# Power_Sensing.net
KiCad netlist of a schematic drawn in Altium Designer
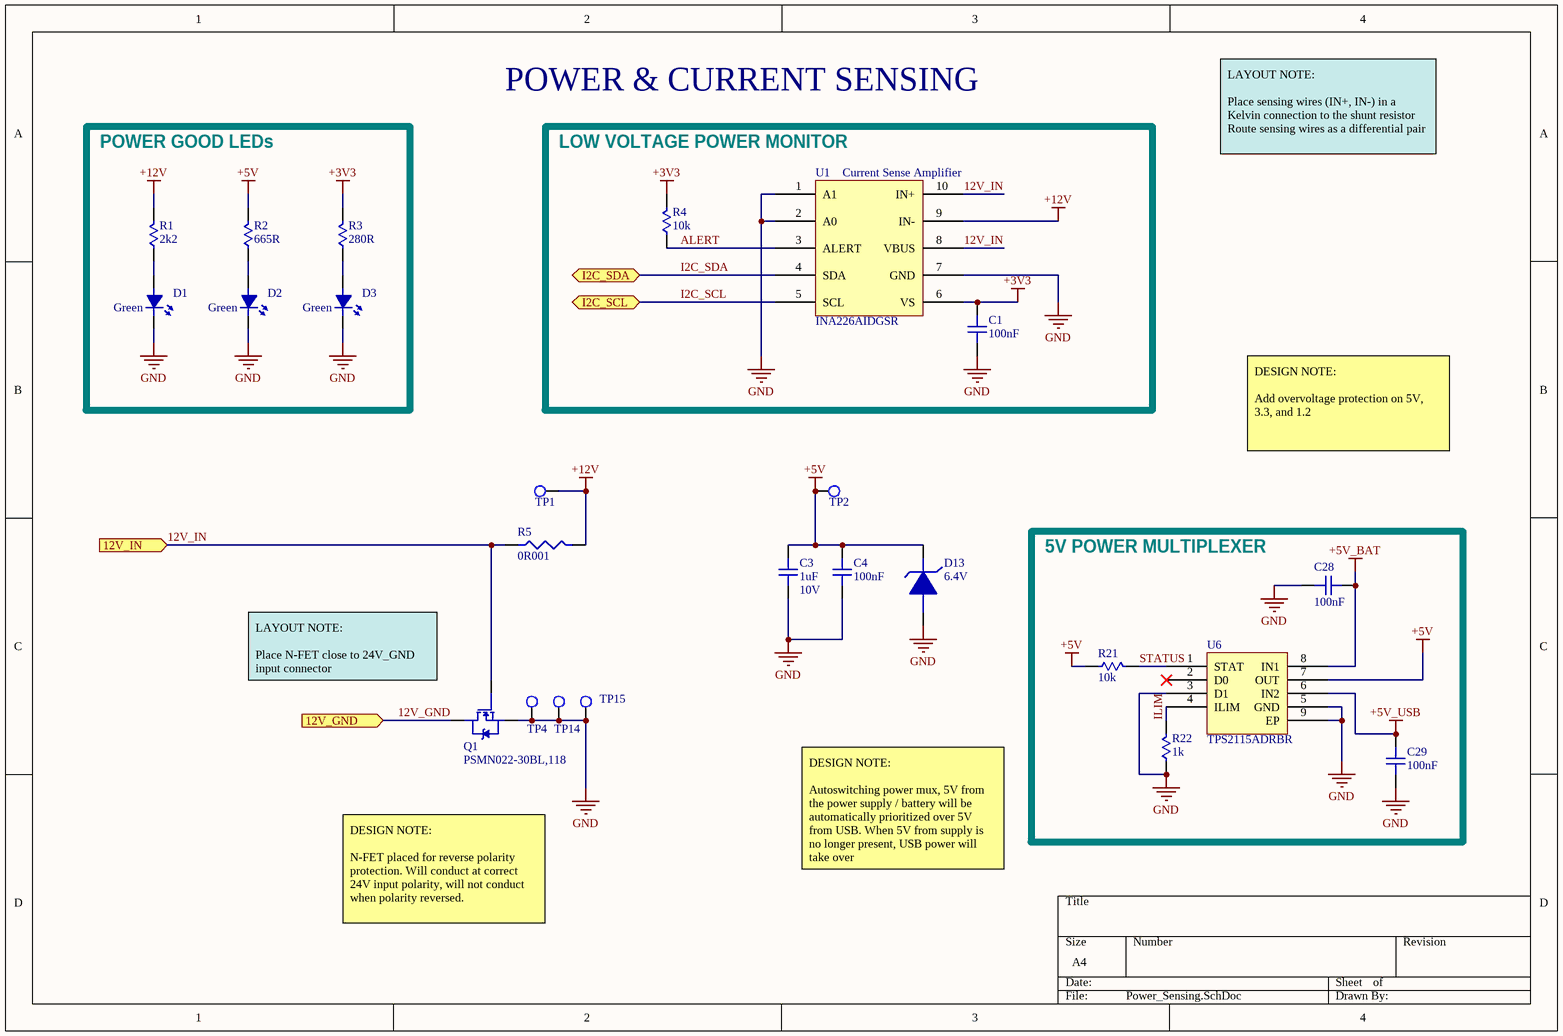
[diagram p0: Power_Sensing.SchDoc]

(export (version "E")
  (design (tool "Eeschema 10.0.6"))
  (components
    (comp (ref "C1")
      (value "100nF")
      (footprint "C0402")
      (description "CAP MLCC 0.1uF 10V X5R 0402 20% SMD 0402 85C Paper T/R")
      (fields
        (field (name "MANUFACTURER") "Samsung")
        (field (name "MANUFACTURER PART NUMBER") "CL05A104MP5NNNC")
      )
      (libsource (lib "PHANTOM_LIBRARY") (part "CL05A104MP5NNNC"))
    )
    (comp (ref "C3")
      (value "1uF")
      (footprint "C0402")
      (description "CAP MLCC 1uF 10V 0402 X5R 20% SMD 0402 85C Paper T/R")
      (fields
        (field (name "MANUFACTURER") "Samsung")
        (field (name "MANUFACTURER PART NUMBER") "CL05A105MP5NNNC")
        (field (name "VOLTAGE RATING") "10V")
      )
      (libsource (lib "PHANTOM_LIBRARY") (part "CL05A105MP5NNNC"))
    )
    (comp (ref "C4")
      (value "100nF")
      (footprint "C0402")
      (description "CAP MLCC 0.1uF 10V X5R 0402 20% SMD 0402 85C Paper T/R")
      (fields
        (field (name "MANUFACTURER") "Samsung")
        (field (name "MANUFACTURER PART NUMBER") "CL05A104MP5NNNC")
      )
      (libsource (lib "PHANTOM_LIBRARY") (part "CL05A104MP5NNNC"))
    )
    (comp (ref "C28")
      (value "100nF")
      (footprint "C0402")
      (description "CAP MLCC 0.1uF 10V X5R 0402 20% SMD 0402 85C Paper T/R")
      (fields
        (field (name "MANUFACTURER") "Samsung")
        (field (name "MANUFACTURER PART NUMBER") "CL05A104MP5NNNC")
      )
      (libsource (lib "PHANTOM_LIBRARY") (part "CL05A104MP5NNNC"))
    )
    (comp (ref "C29")
      (value "100nF")
      (footprint "C0402")
      (description "CAP MLCC 0.1uF 10V X5R 0402 20% SMD 0402 85C Paper T/R")
      (fields
        (field (name "MANUFACTURER") "Samsung")
        (field (name "MANUFACTURER PART NUMBER") "CL05A104MP5NNNC")
      )
      (libsource (lib "PHANTOM_LIBRARY") (part "CL05A104MP5NNNC"))
    )
    (comp (ref "D1")
      (value "Green")
      (footprint "LED_0603")
      (description "LED GREEN CLEAR 0603 SMD  LED, 0603, B GREEN,  40MCD, 570NM")
      (fields
        (field (name "MANUFACTURER") "Wurth Electronics")
        (field (name "MANUFACTURER PART NUMBER") "150060VS75000")
      )
      (libsource (lib "PHANTOM_LIBRARY") (part "150060VS75000"))
    )
    (comp (ref "D2")
      (value "Green")
      (footprint "LED_0603")
      (description "LED GREEN CLEAR 0603 SMD  LED, 0603, B GREEN,  40MCD, 570NM")
      (fields
        (field (name "MANUFACTURER") "Wurth Electronics")
        (field (name "MANUFACTURER PART NUMBER") "150060VS75000")
      )
      (libsource (lib "PHANTOM_LIBRARY") (part "150060VS75000"))
    )
    (comp (ref "D3")
      (value "Green")
      (footprint "LED_0603")
      (description "LED GREEN CLEAR 0603 SMD  LED, 0603, B GREEN,  40MCD, 570NM")
      (fields
        (field (name "MANUFACTURER") "Wurth Electronics")
        (field (name "MANUFACTURER PART NUMBER") "150060VS75000")
      )
      (libsource (lib "PHANTOM_LIBRARY") (part "150060VS75000"))
    )
    (comp (ref "D13")
      (value "6.4V")
      (footprint "DIODE_TVS")
      (description "DIODE TVS_6V4 5VWM 9.2VC SMA")
      (fields (field (name "MANUFACTURER") "Littelfuse") (field (name "MANUFACTURER PART NUMBER") "SMAJ5.0A"))
      (libsource (lib "PHANTOM_LIBRARY") (part "SMAJ5.0A"))
    )
    (comp (ref "Q1")
      (value "PSMN022-30BL,118")
      (footprint "D2PAK_FETs")
      (description "MOSFET N-CH 30V 30A 22.6mOhm Rds(ON)")
      (fields (field (name "MANUFACTURER") "NXP Semiconductors"))
      (libsource (lib "PHANTOM_LIBRARY") (part "PSMN022-30BL,118"))
    )
    (comp (ref "R1")
      (value "2k2")
      (footprint "R0402")
      (description "RES SMD 2.2K OHM 5% 1/16W 0402")
      (fields
        (field (name "MANUFACTURER") "Yageo")
        (field (name "MANUFACTURER PART NUMBER") "RC0402JR-072K2L")
      )
      (libsource (lib "PHANTOM_LIBRARY") (part "RC0402JR-072K2L"))
    )
    (comp (ref "R2")
      (value "665R")
      (footprint "R0402")
      (description "RES SMD 665 OHM 1% 0402 1/16W")
      (fields
        (field (name "MANUFACTURER") "Yageo")
        (field (name "MANUFACTURER PART NUMBER") "RC0402FR-07665RL")
      )
      (libsource (lib "PHANTOM_LIBRARY") (part "RC0402FR-07665RL"))
    )
    (comp (ref "R3")
      (value "280R")
      (footprint "R0402")
      (description "RES SMD 280 OHM 1% 1/16W 0402")
      (fields
        (field (name "MANUFACTURER") "Yageo")
        (field (name "MANUFACTURER PART NUMBER") "RC0402FR-07280RL")
      )
      (libsource (lib "PHANTOM_LIBRARY") (part "RC0402FR-07280RL"))
    )
    (comp (ref "R4")
      (value "10k")
      (footprint "R0402")
      (description "RES SMD 10K OHM 5% 1/16W 0402")
      (fields
        (field (name "MANUFACTURER") "Yageo")
        (field (name "MANUFACTURER PART NUMBER") "RC0402JR-0710KL")
      )
      (libsource (lib "PHANTOM_LIBRARY") (part "RC0402JR-0710KL"))
    )
    (comp (ref "R5")
      (value "0R001")
      (footprint "R2512")
      (description "Res Thick Film 2512 0.001 Ohm 1% 1W 250ppm/C to 450ppm/C Molded SMD Embossed Carrier T/R")
      (fields
        (field (name "MANUFACTURER") "Panasonic ECG")
        (field (name "MANUFACTURER PART NUMBER") "ERJ-M1WTF1M0U")
      )
      (libsource (lib "PHANTOM_LIBRARY") (part "ERJ-M1WTF1M0U"))
    )
    (comp (ref "R21")
      (value "10k")
      (footprint "R0402")
      (description "RES SMD 10K OHM 5% 1/16W 0402")
      (fields
        (field (name "MANUFACTURER") "Yageo")
        (field (name "MANUFACTURER PART NUMBER") "RC0402JR-0710KL")
      )
      (libsource (lib "PHANTOM_LIBRARY") (part "RC0402JR-0710KL"))
    )
    (comp (ref "R22")
      (value "1k")
      (footprint "R0402")
      (description "RES SMD 1K OHM 0.5% 1/16W 0402")
      (fields
        (field (name "MANUFACTURER") "Susumu")
        (field (name "MANUFACTURER PART NUMBER") "RR0510P-102-D")
      )
      (libsource (lib "PHANTOM_LIBRARY") (part "RR0510P-102-D"))
    )
    (comp (ref "TP1")
      (value "5015")
      (footprint "TP_HOOK")
      (description "TEST POINT, PCB, SMT")
      (fields (field (name "MANUFACTURER") "Keystone Electronics"))
      (libsource (lib "PHANTOM_LIBRARY") (part "5015"))
    )
    (comp (ref "TP2")
      (value "5015")
      (footprint "TP_HOOK")
      (description "TEST POINT, PCB, SMT")
      (fields (field (name "MANUFACTURER") "Keystone Electronics"))
      (libsource (lib "PHANTOM_LIBRARY") (part "5015"))
    )
    (comp (ref "TP4")
      (value "5015")
      (footprint "TP_HOOK")
      (description "TEST POINT, PCB, SMT")
      (fields (field (name "MANUFACTURER") "Keystone Electronics"))
      (libsource (lib "PHANTOM_LIBRARY") (part "5015"))
    )
    (comp (ref "TP14")
      (value "5015")
      (footprint "TP_HOOK")
      (description "TEST POINT, PCB, SMT")
      (fields (field (name "MANUFACTURER") "Keystone Electronics"))
      (libsource (lib "PHANTOM_LIBRARY") (part "5015"))
    )
    (comp (ref "TP15")
      (value "5015")
      (footprint "TP_HOOK")
      (description "TEST POINT, PCB, SMT")
      (fields (field (name "MANUFACTURER") "Keystone Electronics"))
      (libsource (lib "PHANTOM_LIBRARY") (part "5015"))
    )
    (comp (ref "U1")
      (value "INA226AIDGSR")
      (footprint "10-VSSOP_INA226")
      (description "IC MONITOR PWR/CURR BIDIR 10MSOP")
      (fields (field (name "MANUFACTURER") "Texas Instruments"))
      (libsource (lib "PHANTOM_LIBRARY") (part "INA226AIDGSR"))
    )
    (comp (ref "U6")
      (value "TPS2115ADRBR")
      (footprint "VSON-8")
      (description "IC OR CTRLR SRC SELECT 8SON")
      (fields (field (name "MANUFACTURER") "Texas Instruments"))
      (libsource (lib "PHANTOM_LIBRARY") (part "TPS2115ADRBR"))
    )
  )
  (nets
    (net (code "1") (name "+3V3") (class "Default")
      (node (ref "C1") (pin "2") (pinfunction "2_2") (pintype "passive"))
      (node (ref "R3") (pin "2") (pinfunction "2_2") (pintype "passive"))
      (node (ref "R4") (pin "2") (pinfunction "2_2") (pintype "passive"))
      (node (ref "U1") (pin "6") (pinfunction "VS_6") (pintype "passive"))
    )
    (net (code "2") (name "+5V") (class "Default")
      (node (ref "C3") (pin "2") (pinfunction "2_2") (pintype "passive"))
      (node (ref "C4") (pin "2") (pinfunction "2_2") (pintype "passive"))
      (node (ref "D13") (pin "1") (pinfunction "1_1") (pintype "passive"))
      (node (ref "R2") (pin "2") (pinfunction "2_2") (pintype "passive"))
      (node (ref "R21") (pin "1") (pinfunction "1_1") (pintype "passive"))
      (node (ref "TP2") (pin "1") (pinfunction "1_1") (pintype "passive"))
      (node (ref "U6") (pin "7") (pinfunction "OUT_7") (pintype "passive"))
    )
    (net (code "3") (name "+5V_BAT") (class "Default")
      (node (ref "C28") (pin "1") (pinfunction "1_1") (pintype "passive"))
      (node (ref "U6") (pin "8") (pinfunction "IN1_8") (pintype "passive"))
    )
    (net (code "4") (name "+5V_USB") (class "Default")
      (node (ref "C29") (pin "2") (pinfunction "2_2") (pintype "passive"))
      (node (ref "U6") (pin "6") (pinfunction "IN2_6") (pintype "passive"))
    )
    (net (code "5") (name "+12V") (class "Default")
      (node (ref "R1") (pin "2") (pinfunction "2_2") (pintype "passive"))
      (node (ref "R5") (pin "2") (pinfunction "2_2") (pintype "passive"))
      (node (ref "TP1") (pin "1") (pinfunction "1_1") (pintype "passive"))
      (node (ref "U1") (pin "9") (pinfunction "IN-_9") (pintype "passive"))
    )
    (net (code "6") (name "/12V_GND") (class "Default")
      (node (ref "Q1") (pin "4") (pinfunction "4_4") (pintype "passive"))
    )
    (net (code "7") (name "/12V_IN") (class "Default")
      (node (ref "Q1") (pin "1") (pinfunction "1_1") (pintype "passive"))
      (node (ref "R5") (pin "1") (pinfunction "1_1") (pintype "passive"))
      (node (ref "U1") (pin "10") (pinfunction "IN+_10") (pintype "passive"))
      (node (ref "U1") (pin "8") (pinfunction "VBUS_8") (pintype "passive"))
    )
    (net (code "8") (name "/ALERT") (class "Default")
      (node (ref "R4") (pin "1") (pinfunction "1_1") (pintype "passive"))
      (node (ref "U1") (pin "3") (pinfunction "ALERT_3") (pintype "passive"))
    )
    (net (code "9") (name "/I2C_SCL") (class "Default")
      (node (ref "U1") (pin "5") (pinfunction "SCL_5") (pintype "passive"))
    )
    (net (code "10") (name "/I2C_SDA") (class "Default")
      (node (ref "U1") (pin "4") (pinfunction "SDA_4") (pintype "passive"))
    )
    (net (code "11") (name "/ILIM") (class "Default")
      (node (ref "R22") (pin "2") (pinfunction "2_2") (pintype "passive"))
      (node (ref "U6") (pin "4") (pinfunction "ILIM_4") (pintype "passive"))
    )
    (net (code "12") (name "/STATUS") (class "Default")
      (node (ref "R21") (pin "2") (pinfunction "2_2") (pintype "passive"))
      (node (ref "U6") (pin "1") (pinfunction "STAT_1") (pintype "passive"))
    )
    (net (code "13") (name "GND") (class "Default")
      (node (ref "C1") (pin "1") (pinfunction "1_1") (pintype "passive"))
      (node (ref "C28") (pin "2") (pinfunction "2_2") (pintype "passive"))
      (node (ref "C29") (pin "1") (pinfunction "1_1") (pintype "passive"))
      (node (ref "C3") (pin "1") (pinfunction "1_1") (pintype "passive"))
      (node (ref "C4") (pin "1") (pinfunction "1_1") (pintype "passive"))
      (node (ref "D1") (pin "2") (pinfunction "2_2") (pintype "passive"))
      (node (ref "D13") (pin "2") (pinfunction "2_2") (pintype "passive"))
      (node (ref "D2") (pin "2") (pinfunction "2_2") (pintype "passive"))
      (node (ref "D3") (pin "2") (pinfunction "2_2") (pintype "passive"))
      (node (ref "Q1") (pin "3") (pinfunction "3_3") (pintype "passive"))
      (node (ref "R22") (pin "1") (pinfunction "1_1") (pintype "passive"))
      (node (ref "TP14") (pin "1") (pinfunction "1_1") (pintype "passive"))
      (node (ref "TP15") (pin "1") (pinfunction "1_1") (pintype "passive"))
      (node (ref "TP4") (pin "1") (pinfunction "1_1") (pintype "passive"))
      (node (ref "U1") (pin "1") (pinfunction "A1_1") (pintype "passive"))
      (node (ref "U1") (pin "2") (pinfunction "A0_2") (pintype "passive"))
      (node (ref "U1") (pin "7") (pinfunction "GND_7") (pintype "passive"))
      (node (ref "U6") (pin "3") (pinfunction "D1_3") (pintype "passive"))
      (node (ref "U6") (pin "5") (pinfunction "GND_5") (pintype "passive"))
      (node (ref "U6") (pin "9") (pinfunction "EP_9") (pintype "passive"))
    )
    (net (code "14") (name "Net-(D1-Pad1)") (class "Default")
      (node (ref "D1") (pin "1") (pinfunction "1_1") (pintype "passive"))
      (node (ref "R1") (pin "1") (pinfunction "1_1") (pintype "passive"))
    )
    (net (code "15") (name "Net-(D2-Pad1)") (class "Default")
      (node (ref "D2") (pin "1") (pinfunction "1_1") (pintype "passive"))
      (node (ref "R2") (pin "1") (pinfunction "1_1") (pintype "passive"))
    )
    (net (code "16") (name "Net-(D3-Pad1)") (class "Default")
      (node (ref "D3") (pin "1") (pinfunction "1_1") (pintype "passive"))
      (node (ref "R3") (pin "1") (pinfunction "1_1") (pintype "passive"))
    )
    (net (code "17") (name "unconnected-(U6-D0-Pad2)") (class "Default")
      (node (ref "U6") (pin "2") (pinfunction "D0_2") (pintype "passive+no_connect"))
    )
  )
)
